# LED_aluminum.net
KiCad netlist of a schematic drawn in Altium Designer
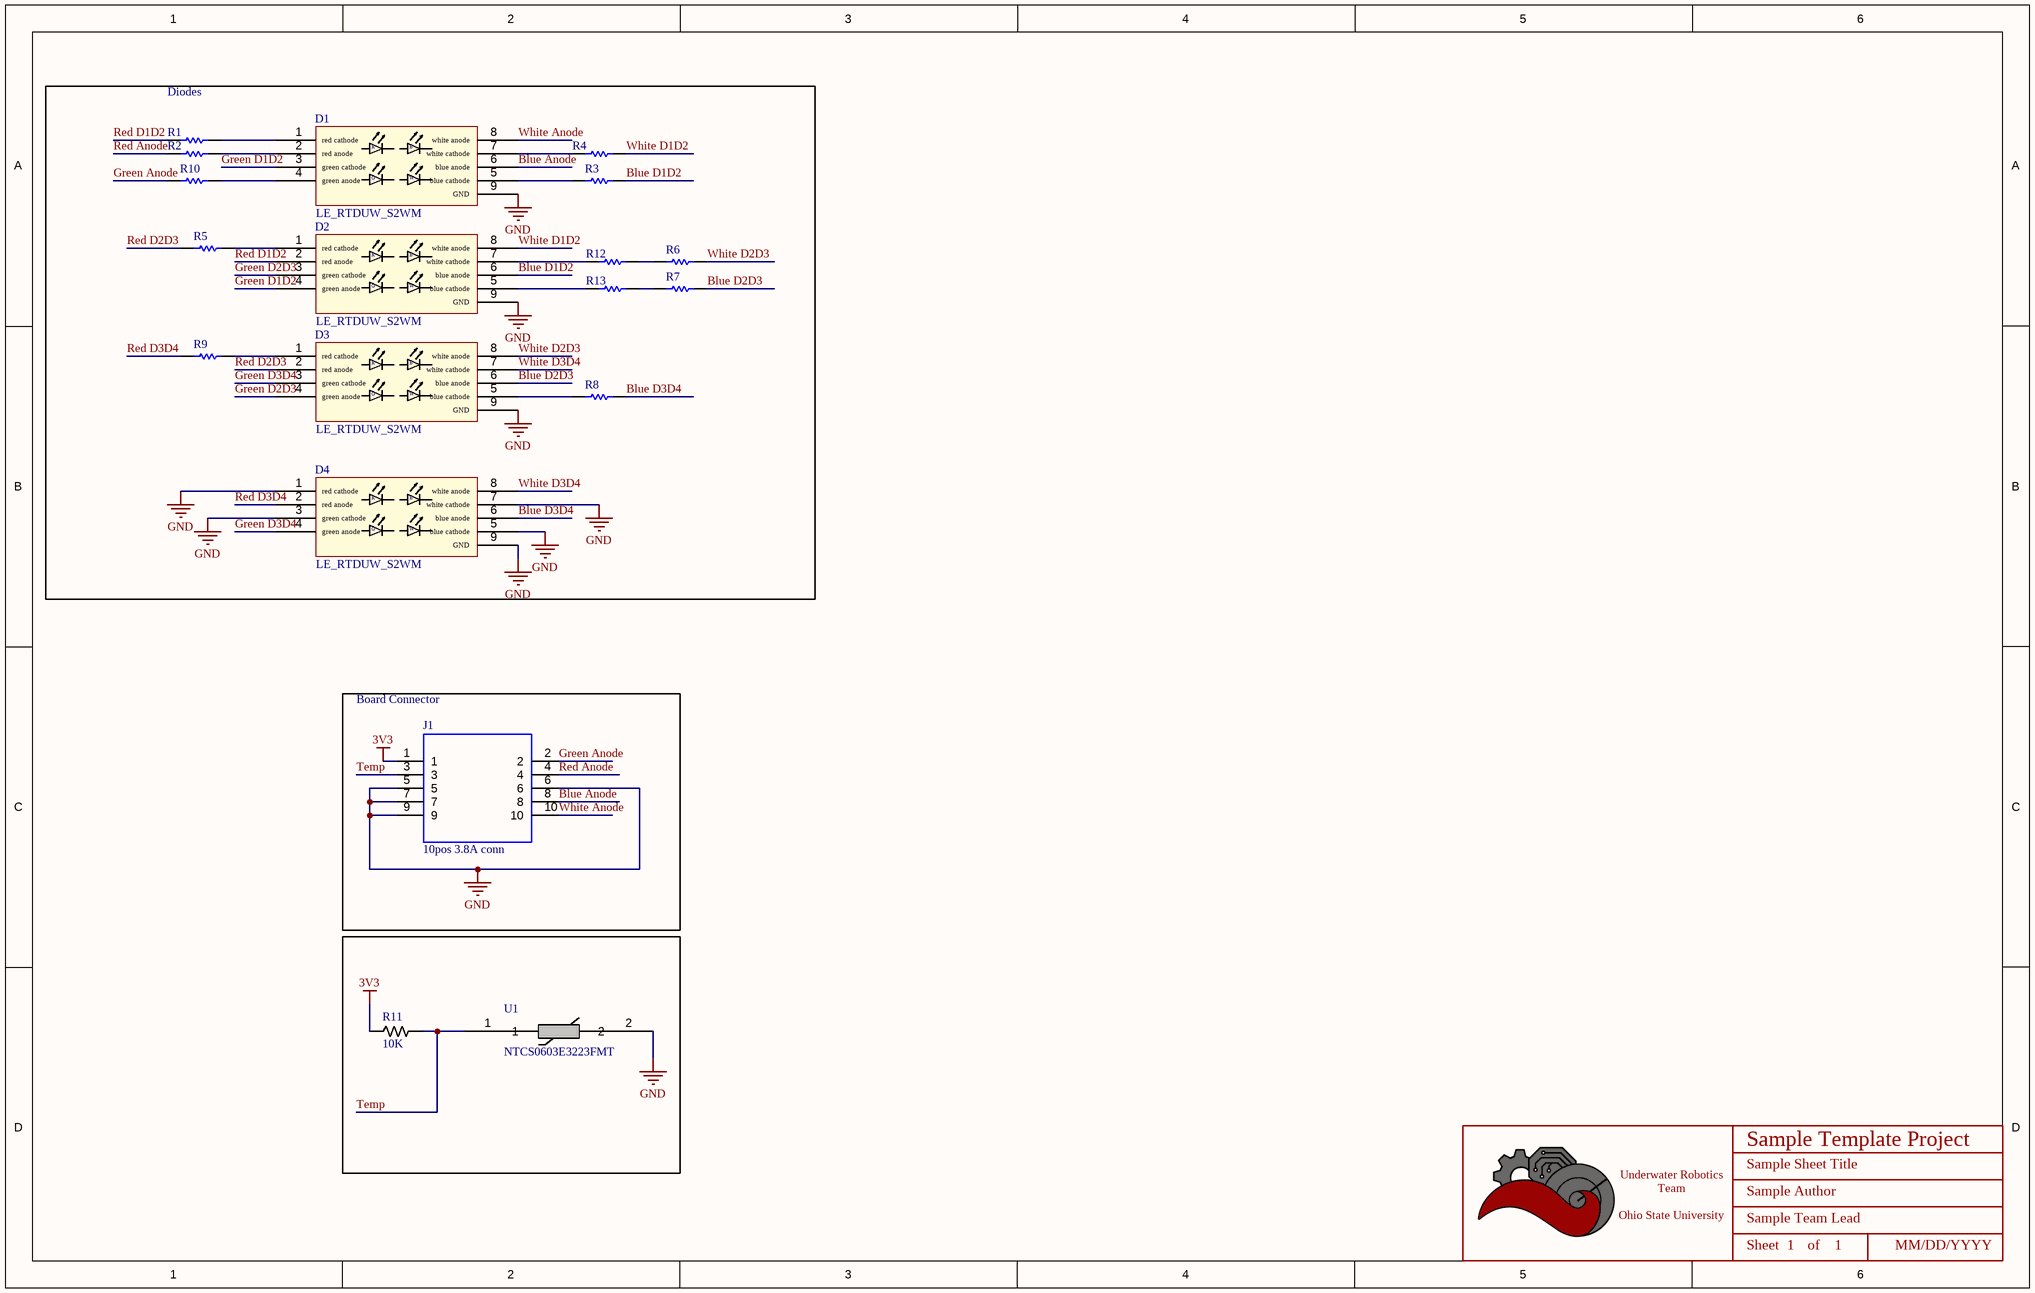
[diagram p0: LED_aluminum.SchDoc]

(export (version "E")
  (design (tool "Eeschema 10.0.6"))
  (components
    (comp (ref "*")
      (value "Title_Block")
      (footprint "LOGO")
      (description "UWRT Schematic Title Block Template\r\n\r\nCreated June 2021, Dylan Trainor")
      (libsource (lib "UWRT") (part "Title_Block"))
    )
    (comp (ref "D1")
      (value "LE_RTDUW_S2WM")
      (footprint "LE_RTDUW_S2WM")
      (description "LED OSTAR RGBW 625/527/453NM SMD")
      (libsource (lib "Diodes") (part "LE_RTDUW_S2WM"))
    )
    (comp (ref "D2")
      (value "LE_RTDUW_S2WM")
      (footprint "LE_RTDUW_S2WM")
      (description "LED OSTAR RGBW 625/527/453NM SMD")
      (libsource (lib "Diodes") (part "LE_RTDUW_S2WM"))
    )
    (comp (ref "D3")
      (value "LE_RTDUW_S2WM")
      (footprint "LE_RTDUW_S2WM")
      (description "LED OSTAR RGBW 625/527/453NM SMD")
      (libsource (lib "Diodes") (part "LE_RTDUW_S2WM"))
    )
    (comp (ref "D4")
      (value "LE_RTDUW_S2WM")
      (footprint "LE_RTDUW_S2WM")
      (description "LED OSTAR RGBW 625/527/453NM SMD")
      (libsource (lib "Diodes") (part "LE_RTDUW_S2WM"))
    )
    (comp (ref "J1")
      (value "10pos 3.8A conn")
      (footprint "SAMTEC-LS2-105-01-X-D-RA2")
      (description "10 Position Connector Self Mating, Non-Gendered, Hermaphroditic Through Hole, Right Angle Gold")
      (fields (field (name "MP") "SAMTEC-LS2-105-01-X-D-RA2"))
      (libsource (lib "Connectors") (part "SAMTEC-LS2-105-01-X-D-RA2"))
    )
    (comp (ref "R1")
      (value "Jumper 2512(6432)")
      (footprint "RESC2512(6432)_L")
      (description "Jumper 2512 (6432 Metric)")
      (fields (field (name "TOLERANCE") "None"))
      (libsource (lib "Altium Content Vault") (part "RES"))
    )
    (comp (ref "R2")
      (value "ERJ-8GEY0R00V")
      (footprint "RESC3216X70X50NL05T20")
      (fields (field (name "MANUFACTURER") "Panasonic"))
      (libsource (lib "Altium Content Vault") (part "RES"))
    )
    (comp (ref "R3")
      (value "Jumper 2512(6432)")
      (footprint "RESC2512(6432)_L")
      (description "Jumper 2512 (6432 Metric)")
      (fields (field (name "TOLERANCE") "None"))
      (libsource (lib "Altium Content Vault") (part "RES"))
    )
    (comp (ref "R4")
      (value "ERJ-8GEY0R00V")
      (footprint "RESC3216X70X50NL05T20")
      (fields (field (name "MANUFACTURER") "Panasonic"))
      (libsource (lib "Altium Content Vault") (part "RES"))
    )
    (comp (ref "R5")
      (value "Jumper 2512(6432)")
      (footprint "RESC2512(6432)_L")
      (description "Jumper 2512 (6432 Metric)")
      (fields (field (name "TOLERANCE") "None"))
      (libsource (lib "Altium Content Vault") (part "RES"))
    )
    (comp (ref "R6")
      (value "Jumper 2512(6432)")
      (footprint "RESC2512(6432)_L")
      (description "Jumper 2512 (6432 Metric)")
      (fields (field (name "TOLERANCE") "None"))
      (libsource (lib "Altium Content Vault") (part "RES"))
    )
    (comp (ref "R7")
      (value "ERJ-8GEY0R00V")
      (footprint "RESC3216X70X50NL05T20")
      (fields (field (name "MANUFACTURER") "Panasonic"))
      (libsource (lib "Altium Content Vault") (part "RES"))
    )
    (comp (ref "R8")
      (value "ERJ-8GEY0R00V")
      (footprint "RESC3216X70X50NL05T20")
      (fields (field (name "MANUFACTURER") "Panasonic"))
      (libsource (lib "Altium Content Vault") (part "RES"))
    )
    (comp (ref "R9")
      (value "ERJ-8GEY0R00V")
      (footprint "RESC3216X70X50NL05T20")
      (fields (field (name "MANUFACTURER") "Panasonic"))
      (libsource (lib "Altium Content Vault") (part "RES"))
    )
    (comp (ref "R10")
      (value "ERJ-8GEY0R00V")
      (footprint "RESC3216X70X50NL05T20")
      (fields (field (name "MANUFACTURER") "Panasonic"))
      (libsource (lib "Altium Content Vault") (part "RES"))
    )
    (comp (ref "R11")
      (value "10k Ohm 0.5% 1/10W")
      (footprint "RESISTOR_0603")
      (description "RES 10k OHM 0.5% 1/10W 0603")
      (fields
        (field (name "TOLERANCE") "+/- 0.5%")
        (field (name "VALUE  (OHMS)") "10K")
        (field (name "MADE BY") "Robert Pafford")
      )
      (libsource (lib "Resistors") (part "RESISTOR_10K_0.5%_0603"))
    )
    (comp (ref "R12")
      (value "ERJ-8GEY0R00V")
      (footprint "RESC3216X70X50NL05T20")
      (fields (field (name "MANUFACTURER") "Panasonic"))
      (libsource (lib "Altium Content Vault") (part "RES"))
    )
    (comp (ref "R13")
      (value "Jumper 2512(6432)")
      (footprint "RESC2512(6432)_L")
      (description "Jumper 2512 (6432 Metric)")
      (fields (field (name "TOLERANCE") "None"))
      (libsource (lib "Altium Content Vault") (part "RES"))
    )
    (comp (ref "U1")
      (value "NTCS0603E3223FMT")
      (footprint "NTCS0603_VIS")
      (fields (field (name "TOLERANCE") "1%"))
      (libsource (lib "Altium Content Vault") (part "NTCS0603E3223FMT"))
    )
  )
  (nets
    (net (code "1") (name "/Blue Anode") (class "Default")
      (node (ref "D1") (pin "6") (pinfunction "blue_anode_6") (pintype "passive"))
      (node (ref "J1") (pin "8") (pinfunction "8_8") (pintype "passive"))
    )
    (net (code "2") (name "/Blue D1D2") (class "Default")
      (node (ref "D2") (pin "6") (pinfunction "blue_anode_6") (pintype "passive"))
      (node (ref "R3") (pin "2") (pinfunction "2_2") (pintype "passive"))
    )
    (net (code "3") (name "/Blue D2D3") (class "Default")
      (node (ref "D3") (pin "6") (pinfunction "blue_anode_6") (pintype "passive"))
      (node (ref "R7") (pin "2") (pinfunction "2_2") (pintype "passive"))
    )
    (net (code "4") (name "/Blue D3D4") (class "Default")
      (node (ref "D4") (pin "6") (pinfunction "blue_anode_6") (pintype "passive"))
      (node (ref "R8") (pin "2") (pinfunction "2_2") (pintype "passive"))
    )
    (net (code "5") (name "/Green Anode") (class "Default")
      (node (ref "J1") (pin "2") (pinfunction "2_2") (pintype "passive"))
      (node (ref "R10") (pin "1") (pinfunction "1_1") (pintype "passive"))
    )
    (net (code "6") (name "/Green D1D2") (class "Default")
      (node (ref "D1") (pin "3") (pinfunction "green_cathode_3") (pintype "passive"))
      (node (ref "D2") (pin "4") (pinfunction "green_anode_4") (pintype "passive"))
    )
    (net (code "7") (name "/Green D2D3") (class "Default")
      (node (ref "D2") (pin "3") (pinfunction "green_cathode_3") (pintype "passive"))
      (node (ref "D3") (pin "4") (pinfunction "green_anode_4") (pintype "passive"))
    )
    (net (code "8") (name "/Green D3D4") (class "Default")
      (node (ref "D3") (pin "3") (pinfunction "green_cathode_3") (pintype "passive"))
      (node (ref "D4") (pin "4") (pinfunction "green_anode_4") (pintype "passive"))
    )
    (net (code "9") (name "/Red Anode") (class "Default")
      (node (ref "J1") (pin "4") (pinfunction "4_4") (pintype "passive"))
      (node (ref "R2") (pin "1") (pinfunction "1_1") (pintype "passive"))
    )
    (net (code "10") (name "/Red D1D2") (class "Default")
      (node (ref "D2") (pin "2") (pinfunction "red_anode_2") (pintype "passive"))
      (node (ref "R1") (pin "1") (pinfunction "1_1") (pintype "passive"))
    )
    (net (code "11") (name "/Red D2D3") (class "Default")
      (node (ref "D3") (pin "2") (pinfunction "red_anode_2") (pintype "passive"))
      (node (ref "R5") (pin "1") (pinfunction "1_1") (pintype "passive"))
    )
    (net (code "12") (name "/Red D3D4") (class "Default")
      (node (ref "D4") (pin "2") (pinfunction "red_anode_2") (pintype "passive"))
      (node (ref "R9") (pin "1") (pinfunction "1_1") (pintype "passive"))
    )
    (net (code "13") (name "/Temp") (class "Default")
      (node (ref "J1") (pin "3") (pinfunction "3_3") (pintype "passive"))
      (node (ref "R11") (pin "1") (pinfunction "1_1") (pintype "passive"))
      (node (ref "U1") (pin "1") (pinfunction "1_1") (pintype "passive"))
    )
    (net (code "14") (name "/White Anode") (class "Default")
      (node (ref "D1") (pin "8") (pinfunction "white_anode_8") (pintype "passive"))
      (node (ref "J1") (pin "10") (pinfunction "10_10") (pintype "passive"))
    )
    (net (code "15") (name "/White D1D2") (class "Default")
      (node (ref "D2") (pin "8") (pinfunction "white_anode_8") (pintype "passive"))
      (node (ref "R4") (pin "2") (pinfunction "2_2") (pintype "passive"))
    )
    (net (code "16") (name "/White D2D3") (class "Default")
      (node (ref "D3") (pin "8") (pinfunction "white_anode_8") (pintype "passive"))
      (node (ref "R6") (pin "2") (pinfunction "2_2") (pintype "passive"))
    )
    (net (code "17") (name "/White D3D4") (class "Default")
      (node (ref "D3") (pin "7") (pinfunction "white_cathode_7") (pintype "passive"))
      (node (ref "D4") (pin "8") (pinfunction "white_anode_8") (pintype "passive"))
    )
    (net (code "18") (name "3V3") (class "Default")
      (node (ref "J1") (pin "1") (pinfunction "1_1") (pintype "passive"))
      (node (ref "R11") (pin "2") (pinfunction "2_2") (pintype "passive"))
    )
    (net (code "19") (name "GND") (class "Default")
      (node (ref "D1") (pin "9") (pinfunction "GND_9") (pintype "passive"))
      (node (ref "D2") (pin "9") (pinfunction "GND_9") (pintype "passive"))
      (node (ref "D3") (pin "9") (pinfunction "GND_9") (pintype "passive"))
      (node (ref "D4") (pin "1") (pinfunction "red_cathode_1") (pintype "passive"))
      (node (ref "D4") (pin "3") (pinfunction "green_cathode_3") (pintype "passive"))
      (node (ref "D4") (pin "5") (pinfunction "blue_cathode_5") (pintype "passive"))
      (node (ref "D4") (pin "7") (pinfunction "white_cathode_7") (pintype "passive"))
      (node (ref "D4") (pin "9") (pinfunction "GND_9") (pintype "passive"))
      (node (ref "J1") (pin "5") (pinfunction "5_5") (pintype "passive"))
      (node (ref "J1") (pin "6") (pinfunction "6_6") (pintype "passive"))
      (node (ref "J1") (pin "7") (pinfunction "7_7") (pintype "passive"))
      (node (ref "J1") (pin "9") (pinfunction "9_9") (pintype "passive"))
      (node (ref "U1") (pin "2") (pinfunction "2_2") (pintype "passive"))
    )
    (net (code "20") (name "Net-(D1-blue_cathode)") (class "Default")
      (node (ref "D1") (pin "5") (pinfunction "blue_cathode_5") (pintype "passive"))
      (node (ref "R3") (pin "1") (pinfunction "1_1") (pintype "passive"))
    )
    (net (code "21") (name "Net-(D1-green_anode)") (class "Default")
      (node (ref "D1") (pin "4") (pinfunction "green_anode_4") (pintype "passive"))
      (node (ref "R10") (pin "2") (pinfunction "2_2") (pintype "passive"))
    )
    (net (code "22") (name "Net-(D1-red_anode)") (class "Default")
      (node (ref "D1") (pin "2") (pinfunction "red_anode_2") (pintype "passive"))
      (node (ref "R2") (pin "2") (pinfunction "2_2") (pintype "passive"))
    )
    (net (code "23") (name "Net-(D1-red_cathode)") (class "Default")
      (node (ref "D1") (pin "1") (pinfunction "red_cathode_1") (pintype "passive"))
      (node (ref "R1") (pin "2") (pinfunction "2_2") (pintype "passive"))
    )
    (net (code "24") (name "Net-(D1-white_cathode)") (class "Default")
      (node (ref "D1") (pin "7") (pinfunction "white_cathode_7") (pintype "passive"))
      (node (ref "R4") (pin "1") (pinfunction "1_1") (pintype "passive"))
    )
    (net (code "25") (name "Net-(D2-blue_cathode)") (class "Default")
      (node (ref "D2") (pin "5") (pinfunction "blue_cathode_5") (pintype "passive"))
      (node (ref "R13") (pin "1") (pinfunction "1_1") (pintype "passive"))
    )
    (net (code "26") (name "Net-(D2-red_cathode)") (class "Default")
      (node (ref "D2") (pin "1") (pinfunction "red_cathode_1") (pintype "passive"))
      (node (ref "R5") (pin "2") (pinfunction "2_2") (pintype "passive"))
    )
    (net (code "27") (name "Net-(D2-white_cathode)") (class "Default")
      (node (ref "D2") (pin "7") (pinfunction "white_cathode_7") (pintype "passive"))
      (node (ref "R12") (pin "1") (pinfunction "1_1") (pintype "passive"))
    )
    (net (code "28") (name "Net-(D3-blue_cathode)") (class "Default")
      (node (ref "D3") (pin "5") (pinfunction "blue_cathode_5") (pintype "passive"))
      (node (ref "R8") (pin "1") (pinfunction "1_1") (pintype "passive"))
    )
    (net (code "29") (name "Net-(D3-red_cathode)") (class "Default")
      (node (ref "D3") (pin "1") (pinfunction "red_cathode_1") (pintype "passive"))
      (node (ref "R9") (pin "2") (pinfunction "2_2") (pintype "passive"))
    )
    (net (code "30") (name "Net-(R12-Pad2)") (class "Default")
      (node (ref "R12") (pin "2") (pinfunction "2_2") (pintype "passive"))
      (node (ref "R6") (pin "1") (pinfunction "1_1") (pintype "passive"))
    )
    (net (code "31") (name "Net-(R13-Pad2)") (class "Default")
      (node (ref "R13") (pin "2") (pinfunction "2_2") (pintype "passive"))
      (node (ref "R7") (pin "1") (pinfunction "1_1") (pintype "passive"))
    )
  )
)
